# Predajnik.net
KiCad netlist of a schematic drawn in Altium Designer
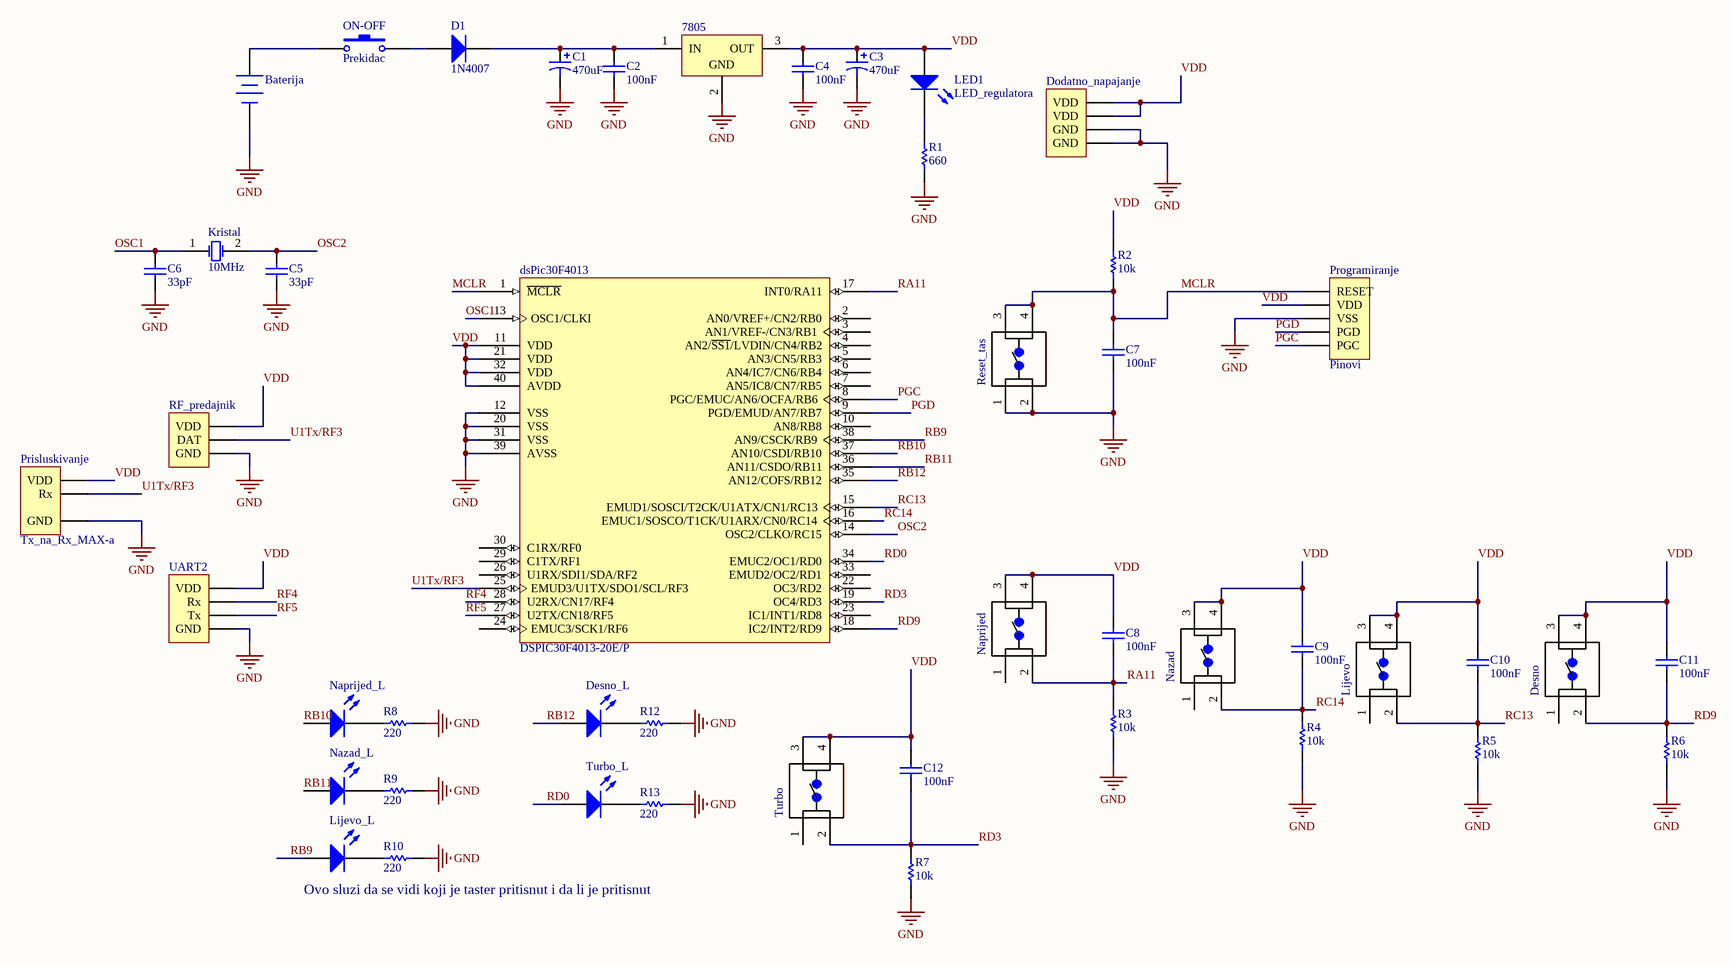
[diagram p0: Predajnik.SchDoc]

(export (version "E")
  (design (tool "Eeschema 10.0.6"))
  (components
    (comp (ref "7805")
      (value "LM7805CT")
      (footprint "T03B")
      (description "3-Terminal Negative Regulator, 3-pin TO-220")
      (fields
        (field (name "PARTNUMBER") "LM7905CT")
        (field (name "MANUFACTURER") "National Semiconductor")
        (field (name "PUBLISHER") "Altium Limited")
      )
      (libsource (lib "NSC LDO") (part "LM7905CT"))
    )
    (comp (ref "Baterija")
      (value "9V")
      (footprint "BAT-2")
      (description "Multicell Battery")
      (fields (field (name "PUBLISHER") "Altium Limited"))
      (libsource (lib "Miscellaneous Devices") (part "Battery"))
    )
    (comp (ref "C1")
      (value "470uF")
      (footprint "El. Kondenzator 470uf")
      (description "Polarized Capacitor (Radial)")
      (fields (field (name "PUBLISHER") "Altium Limited"))
      (libsource (lib "Miscellaneous Devices") (part "Cap Pol1"))
    )
    (comp (ref "C2")
      (value "100nF")
      (footprint "C blok 100n")
      (description "Capacitor")
      (fields (field (name "PUBLISHER") "Altium Limited"))
      (libsource (lib "Miscellaneous Devices") (part "Cap"))
    )
    (comp (ref "C3")
      (value "470uF")
      (footprint "El. Kondenzator 470uf")
      (description "Polarized Capacitor (Radial)")
      (fields (field (name "PUBLISHER") "Altium Limited"))
      (libsource (lib "Miscellaneous Devices") (part "Cap Pol1"))
    )
    (comp (ref "C4")
      (value "100nF")
      (footprint "C blok 100n")
      (description "Capacitor")
      (fields (field (name "PUBLISHER") "Altium Limited"))
      (libsource (lib "Miscellaneous Devices") (part "Cap"))
    )
    (comp (ref "C5")
      (value "33pF")
      (footprint "C keramicki 30pF")
      (description "Capacitor")
      (fields (field (name "PUBLISHER") "Altium Limited"))
      (libsource (lib "Miscellaneous Devices") (part "Cap"))
    )
    (comp (ref "C6")
      (value "33pF")
      (footprint "C keramicki 30pF")
      (description "Capacitor")
      (fields (field (name "PUBLISHER") "Altium Limited"))
      (libsource (lib "Miscellaneous Devices") (part "Cap"))
    )
    (comp (ref "C7")
      (value "100nF")
      (footprint "C blok 100n")
      (description "Capacitor")
      (fields (field (name "PUBLISHER") "Altium Limited"))
      (libsource (lib "Miscellaneous Devices") (part "Cap"))
    )
    (comp (ref "C8")
      (value "100nF")
      (footprint "C blok 100n")
      (description "Capacitor")
      (fields (field (name "PUBLISHER") "Altium Limited"))
      (libsource (lib "Miscellaneous Devices") (part "Cap"))
    )
    (comp (ref "C9")
      (value "100nF")
      (footprint "C blok 100n")
      (description "Capacitor")
      (fields (field (name "PUBLISHER") "Altium Limited"))
      (libsource (lib "Miscellaneous Devices") (part "Cap"))
    )
    (comp (ref "C10")
      (value "100nF")
      (footprint "C blok 100n")
      (description "Capacitor")
      (fields (field (name "PUBLISHER") "Altium Limited"))
      (libsource (lib "Miscellaneous Devices") (part "Cap"))
    )
    (comp (ref "C11")
      (value "100nF")
      (footprint "C blok 100n")
      (description "Capacitor")
      (fields (field (name "PUBLISHER") "Altium Limited"))
      (libsource (lib "Miscellaneous Devices") (part "Cap"))
    )
    (comp (ref "C12")
      (value "100nF")
      (footprint "C blok 100n")
      (description "Capacitor")
      (fields (field (name "PUBLISHER") "Altium Limited"))
      (libsource (lib "Miscellaneous Devices") (part "Cap"))
    )
    (comp (ref "D1")
      (value "1N4007")
      (footprint "DO-41")
      (description "1 Amp General Purpose Rectifier")
      (fields (field (name "PUBLISHER") "Altium Limited"))
      (libsource (lib "Miscellaneous Devices") (part "Diode 1N4007"))
    )
    (comp (ref "Desno")
      (value "3-1825910-1")
      (footprint "*TE_3-1825910-1")
      (description "Switch Push Button OFF _ON_ SPST Round Button 0.05A 24VDC Momentary Contact PC Pins Thru-Hole")
      (fields (field (name "MF") "TE Connectivity"))
      (libsource (lib "3-1825910-1") (part "3-1825910-1"))
    )
    (comp (ref "Desno_L")
      (value "LED0")
      (footprint "LED_5mm")
      (description "Typical INFRARED GaAs LED")
      (fields (field (name "PUBLISHER") "Altium Limited"))
      (libsource (lib "Miscellaneous Devices") (part "LED0"))
    )
    (comp (ref "Dodatno_napajanje")
      (value "~")
      (footprint "HDR1X4")
      (description "Header, 4-Pin")
      (fields (field (name "PUBLISHER") "Altium Limited"))
      (libsource (lib "") (part "Header 4_2"))
    )
    (comp (ref "dsPic30F4013")
      (value "DSPIC30F4013-20E/P")
      (footprint "PDIP600-P40")
      (fields (field (name "PUBLISHER") "Altium Limited"))
      (libsource (lib "Microchip DSC 16-Bit dsPIC30F") (part "DSPIC30F4013-20E/P"))
    )
    (comp (ref "Kristal")
      (value "10MHz")
      (footprint "R38")
      (description "Crystal Oscillator")
      (fields (field (name "PUBLISHER") "Altium Limited"))
      (libsource (lib "Miscellaneous Devices") (part "XTAL"))
    )
    (comp (ref "LED1")
      (value "LED_regulatora")
      (footprint "LED_5mm")
      (description "Typical RED GaAs LED")
      (fields (field (name "PUBLISHER") "Altium Limited"))
      (libsource (lib "Miscellaneous Devices") (part "LED1"))
    )
    (comp (ref "Lijevo")
      (value "3-1825910-1")
      (footprint "*TE_3-1825910-1")
      (description "Switch Push Button OFF _ON_ SPST Round Button 0.05A 24VDC Momentary Contact PC Pins Thru-Hole")
      (fields (field (name "MF") "TE Connectivity"))
      (libsource (lib "3-1825910-1") (part "3-1825910-1"))
    )
    (comp (ref "Lijevo_L")
      (value "LED0")
      (footprint "LED_5mm")
      (description "Typical INFRARED GaAs LED")
      (fields (field (name "PUBLISHER") "Altium Limited"))
      (libsource (lib "Miscellaneous Devices") (part "LED0"))
    )
    (comp (ref "Naprijed")
      (value "3-1825910-1")
      (footprint "*TE_3-1825910-1")
      (description "Switch Push Button OFF _ON_ SPST Round Button 0.05A 24VDC Momentary Contact PC Pins Thru-Hole")
      (fields (field (name "MF") "TE Connectivity"))
      (libsource (lib "3-1825910-1") (part "3-1825910-1"))
    )
    (comp (ref "Naprijed_L")
      (value "LED0")
      (footprint "LED_5mm")
      (description "Typical INFRARED GaAs LED")
      (fields (field (name "PUBLISHER") "Altium Limited"))
      (libsource (lib "Miscellaneous Devices") (part "LED0"))
    )
    (comp (ref "Nazad")
      (value "3-1825910-1")
      (footprint "*TE_3-1825910-1")
      (description "Switch Push Button OFF _ON_ SPST Round Button 0.05A 24VDC Momentary Contact PC Pins Thru-Hole")
      (fields (field (name "MF") "TE Connectivity"))
      (libsource (lib "3-1825910-1") (part "3-1825910-1"))
    )
    (comp (ref "Nazad_L")
      (value "LED0")
      (footprint "LED_5mm")
      (description "Typical INFRARED GaAs LED")
      (fields (field (name "PUBLISHER") "Altium Limited"))
      (libsource (lib "Miscellaneous Devices") (part "LED0"))
    )
    (comp (ref "ON-OFF")
      (value "Prekidac")
      (footprint "SPST-2")
      (description "Switch")
      (fields (field (name "PUBLISHER") "Altium Limited"))
      (libsource (lib "Miscellaneous Devices") (part "SW-PB"))
    )
    (comp (ref "Prisluskivanje")
      (value "Tx_na_Rx_MAX-a")
      (footprint "HDR1X3")
      (description "Header, 4-Pin")
      (fields (field (name "PUBLISHER") "Altium Limited"))
      (libsource (lib "Miscellaneous Connectors") (part "Header 4"))
    )
    (comp (ref "Programiranje")
      (value "Pinovi")
      (footprint "HDR1X5")
      (description "Header, 5-Pin")
      (fields (field (name "PUBLISHER") "Altium Limited"))
      (libsource (lib "Miscellaneous Connectors") (part "Header 5"))
    )
    (comp (ref "R1")
      (value "660")
      (footprint "AXIAL-0.3")
      (description "Resistor")
      (fields (field (name "PUBLISHER") "Altium Limited"))
      (libsource (lib "Miscellaneous Devices") (part "Res1"))
    )
    (comp (ref "R2")
      (value "10k")
      (footprint "AXIAL-0.3")
      (description "Resistor")
      (fields (field (name "PUBLISHER") "Altium Limited"))
      (libsource (lib "Miscellaneous Devices") (part "Res1"))
    )
    (comp (ref "R3")
      (value "10k")
      (footprint "AXIAL-0.3")
      (description "Resistor")
      (fields (field (name "PUBLISHER") "Altium Limited"))
      (libsource (lib "Miscellaneous Devices") (part "Res1"))
    )
    (comp (ref "R4")
      (value "10k")
      (footprint "AXIAL-0.3")
      (description "Resistor")
      (fields (field (name "PUBLISHER") "Altium Limited"))
      (libsource (lib "Miscellaneous Devices") (part "Res1"))
    )
    (comp (ref "R5")
      (value "10k")
      (footprint "AXIAL-0.3")
      (description "Resistor")
      (fields (field (name "PUBLISHER") "Altium Limited"))
      (libsource (lib "Miscellaneous Devices") (part "Res1"))
    )
    (comp (ref "R6")
      (value "10k")
      (footprint "AXIAL-0.3")
      (description "Resistor")
      (fields (field (name "PUBLISHER") "Altium Limited"))
      (libsource (lib "Miscellaneous Devices") (part "Res1"))
    )
    (comp (ref "R7")
      (value "10k")
      (footprint "AXIAL-0.3")
      (description "Resistor")
      (fields (field (name "PUBLISHER") "Altium Limited"))
      (libsource (lib "Miscellaneous Devices") (part "Res1"))
    )
    (comp (ref "R8")
      (value "220")
      (footprint "AXIAL-0.3")
      (description "Resistor")
      (fields (field (name "PUBLISHER") "Altium Limited"))
      (libsource (lib "Miscellaneous Devices") (part "Res1"))
    )
    (comp (ref "R9")
      (value "220")
      (footprint "AXIAL-0.3")
      (description "Resistor")
      (fields (field (name "PUBLISHER") "Altium Limited"))
      (libsource (lib "Miscellaneous Devices") (part "Res1"))
    )
    (comp (ref "R10")
      (value "220")
      (footprint "AXIAL-0.3")
      (description "Resistor")
      (fields (field (name "PUBLISHER") "Altium Limited"))
      (libsource (lib "Miscellaneous Devices") (part "Res1"))
    )
    (comp (ref "R12")
      (value "220")
      (footprint "AXIAL-0.3")
      (description "Resistor")
      (fields (field (name "PUBLISHER") "Altium Limited"))
      (libsource (lib "Miscellaneous Devices") (part "Res1"))
    )
    (comp (ref "R13")
      (value "220")
      (footprint "AXIAL-0.3")
      (description "Resistor")
      (fields (field (name "PUBLISHER") "Altium Limited"))
      (libsource (lib "Miscellaneous Devices") (part "Res1"))
    )
    (comp (ref "Reset_tas")
      (value "3-1825910-1")
      (footprint "*TE_3-1825910-1")
      (description "Switch Push Button OFF _ON_ SPST Round Button 0.05A 24VDC Momentary Contact PC Pins Thru-Hole")
      (fields (field (name "MF") "TE Connectivity"))
      (libsource (lib "3-1825910-1") (part "3-1825910-1"))
    )
    (comp (ref "RF_predajnik")
      (value "Header 3")
      (footprint "HDR1X3")
      (description "Header, 3-Pin")
      (fields (field (name "PUBLISHER") "Altium Limited"))
      (libsource (lib "Miscellaneous Connectors") (part "Header 3"))
    )
    (comp (ref "Turbo")
      (value "3-1825910-1")
      (footprint "*TE_3-1825910-1")
      (description "Switch Push Button OFF _ON_ SPST Round Button 0.05A 24VDC Momentary Contact PC Pins Thru-Hole")
      (fields (field (name "MF") "TE Connectivity"))
      (libsource (lib "3-1825910-1") (part "3-1825910-1"))
    )
    (comp (ref "Turbo_L")
      (value "LED0")
      (footprint "LED_5mm")
      (description "Typical INFRARED GaAs LED")
      (fields (field (name "PUBLISHER") "Altium Limited"))
      (libsource (lib "Miscellaneous Devices") (part "LED0"))
    )
    (comp (ref "UART2")
      (value "~")
      (footprint "HDR1X4")
      (description "Header, 4-Pin")
      (fields (field (name "PUBLISHER") "Altium Limited"))
      (libsource (lib "") (part "Header 4_1"))
    )
  )
  (nets
    (net (code "1") (name "/MCLR") (class "Default")
      (node (ref "C7") (pin "2") (pinfunction "2_2") (pintype "passive"))
      (node (ref "Programiranje") (pin "1") (pinfunction "RESET_1") (pintype "passive"))
      (node (ref "R2") (pin "1") (pinfunction "1_1") (pintype "passive"))
      (node (ref "Reset_tas") (pin "3") (pinfunction "3_3") (pintype "passive"))
      (node (ref "Reset_tas") (pin "4") (pinfunction "4_4") (pintype "passive"))
      (node (ref "dsPic30F4013") (pin "1") (pinfunction "~{MCLR}_1") (pintype "input"))
    )
    (net (code "2") (name "/OSC1") (class "Default")
      (node (ref "C6") (pin "2") (pinfunction "2_2") (pintype "passive"))
      (node (ref "Kristal") (pin "1") (pinfunction "OSC1_1") (pintype "passive"))
      (node (ref "dsPic30F4013") (pin "13") (pinfunction "OSC1/CLKI_13") (pintype "input"))
    )
    (net (code "3") (name "/OSC2") (class "Default")
      (node (ref "C5") (pin "2") (pinfunction "2_2") (pintype "passive"))
      (node (ref "Kristal") (pin "2") (pinfunction "OSC2_2") (pintype "passive"))
      (node (ref "dsPic30F4013") (pin "14") (pinfunction "OSC2/CLKO/RC15_14") (pintype "bidirectional"))
    )
    (net (code "4") (name "/PGC") (class "Default")
      (node (ref "Programiranje") (pin "5") (pinfunction "PGC_5") (pintype "passive"))
      (node (ref "dsPic30F4013") (pin "8") (pinfunction "PGC/EMUC/AN6/OCFA/RB6_8") (pintype "bidirectional"))
    )
    (net (code "5") (name "/PGD") (class "Default")
      (node (ref "Programiranje") (pin "4") (pinfunction "PGD_4") (pintype "passive"))
      (node (ref "dsPic30F4013") (pin "9") (pinfunction "PGD/EMUD/AN7/RB7_9") (pintype "bidirectional"))
    )
    (net (code "6") (name "/RA11") (class "Default")
      (node (ref "C8") (pin "1") (pinfunction "1_1") (pintype "passive"))
      (node (ref "Naprijed") (pin "2") (pinfunction "2_2") (pintype "passive"))
      (node (ref "R3") (pin "2") (pinfunction "2_2") (pintype "passive"))
      (node (ref "dsPic30F4013") (pin "17") (pinfunction "INT0/RA11_17") (pintype "bidirectional"))
    )
    (net (code "7") (name "/RB9") (class "Default")
      (node (ref "Lijevo_L") (pin "1") (pinfunction "A_1") (pintype "passive"))
      (node (ref "dsPic30F4013") (pin "38") (pinfunction "AN9/CSCK/RB9_38") (pintype "bidirectional"))
    )
    (net (code "8") (name "/RB10") (class "Default")
      (node (ref "Naprijed_L") (pin "1") (pinfunction "A_1") (pintype "passive"))
      (node (ref "dsPic30F4013") (pin "37") (pinfunction "AN10/CSDI/RB10_37") (pintype "bidirectional"))
    )
    (net (code "9") (name "/RB11") (class "Default")
      (node (ref "Nazad_L") (pin "1") (pinfunction "A_1") (pintype "passive"))
      (node (ref "dsPic30F4013") (pin "36") (pinfunction "AN11/CSDO/RB11_36") (pintype "bidirectional"))
    )
    (net (code "10") (name "/RB12") (class "Default")
      (node (ref "Desno_L") (pin "1") (pinfunction "A_1") (pintype "passive"))
      (node (ref "dsPic30F4013") (pin "35") (pinfunction "AN12/COFS/RB12_35") (pintype "bidirectional"))
    )
    (net (code "11") (name "/RC13") (class "Default")
      (node (ref "C10") (pin "1") (pinfunction "1_1") (pintype "passive"))
      (node (ref "Lijevo") (pin "2") (pinfunction "2_2") (pintype "passive"))
      (node (ref "R5") (pin "2") (pinfunction "2_2") (pintype "passive"))
      (node (ref "dsPic30F4013") (pin "15") (pinfunction "EMUD1/SOSCI/T2CK/U1ATX/CN1/RC13_15") (pintype "bidirectional"))
    )
    (net (code "12") (name "/RC14") (class "Default")
      (node (ref "C9") (pin "1") (pinfunction "1_1") (pintype "passive"))
      (node (ref "Nazad") (pin "2") (pinfunction "2_2") (pintype "passive"))
      (node (ref "R4") (pin "2") (pinfunction "2_2") (pintype "passive"))
      (node (ref "dsPic30F4013") (pin "16") (pinfunction "EMUC1/SOSCO/T1CK/U1ARX/CN0/RC14_16") (pintype "bidirectional"))
    )
    (net (code "13") (name "/RD0") (class "Default")
      (node (ref "Turbo_L") (pin "1") (pinfunction "A_1") (pintype "passive"))
      (node (ref "dsPic30F4013") (pin "34") (pinfunction "EMUC2/OC1/RD0_34") (pintype "bidirectional"))
    )
    (net (code "14") (name "/RD3") (class "Default")
      (node (ref "C12") (pin "1") (pinfunction "1_1") (pintype "passive"))
      (node (ref "R7") (pin "2") (pinfunction "2_2") (pintype "passive"))
      (node (ref "Turbo") (pin "2") (pinfunction "2_2") (pintype "passive"))
      (node (ref "dsPic30F4013") (pin "19") (pinfunction "OC4/RD3_19") (pintype "bidirectional"))
    )
    (net (code "15") (name "/RD9") (class "Default")
      (node (ref "C11") (pin "1") (pinfunction "1_1") (pintype "passive"))
      (node (ref "Desno") (pin "2") (pinfunction "2_2") (pintype "passive"))
      (node (ref "R6") (pin "2") (pinfunction "2_2") (pintype "passive"))
      (node (ref "dsPic30F4013") (pin "18") (pinfunction "IC2/INT2/RD9_18") (pintype "bidirectional"))
    )
    (net (code "16") (name "/RF4") (class "Default")
      (node (ref "UART2") (pin "2") (pinfunction "Rx_2") (pintype "passive"))
      (node (ref "dsPic30F4013") (pin "28") (pinfunction "U2RX/CN17/RF4_28") (pintype "bidirectional"))
    )
    (net (code "17") (name "/RF5") (class "Default")
      (node (ref "UART2") (pin "3") (pinfunction "Tx_3") (pintype "passive"))
      (node (ref "dsPic30F4013") (pin "27") (pinfunction "U2TX/CN18/RF5_27") (pintype "bidirectional"))
    )
    (net (code "18") (name "/U1Tx{slash}RF3") (class "Default")
      (node (ref "Prisluskivanje") (pin "2") (pinfunction "Rx_2") (pintype "passive"))
      (node (ref "RF_predajnik") (pin "2") (pinfunction "DAT_2") (pintype "passive"))
      (node (ref "dsPic30F4013") (pin "25") (pinfunction "EMUD3/U1TX/SDO1/SCL/RF3_25") (pintype "bidirectional"))
    )
    (net (code "19") (name "/VDD") (class "Default")
      (node (ref "7805") (pin "3") (pinfunction "OUT_3") (pintype "power_in"))
      (node (ref "C10") (pin "2") (pinfunction "2_2") (pintype "passive"))
      (node (ref "C11") (pin "2") (pinfunction "2_2") (pintype "passive"))
      (node (ref "C12") (pin "2") (pinfunction "2_2") (pintype "passive"))
      (node (ref "C3") (pin "1") (pinfunction "1_1") (pintype "passive"))
      (node (ref "C4") (pin "2") (pinfunction "2_2") (pintype "passive"))
      (node (ref "C8") (pin "2") (pinfunction "2_2") (pintype "passive"))
      (node (ref "C9") (pin "2") (pinfunction "2_2") (pintype "passive"))
      (node (ref "Desno") (pin "3") (pinfunction "3_3") (pintype "passive"))
      (node (ref "Desno") (pin "4") (pinfunction "4_4") (pintype "passive"))
      (node (ref "Dodatno_napajanje") (pin "1") (pinfunction "VDD_1") (pintype "passive"))
      (node (ref "Dodatno_napajanje") (pin "2") (pinfunction "VDD_2") (pintype "passive"))
      (node (ref "LED1") (pin "1") (pinfunction "A_1") (pintype "passive"))
      (node (ref "Lijevo") (pin "3") (pinfunction "3_3") (pintype "passive"))
      (node (ref "Lijevo") (pin "4") (pinfunction "4_4") (pintype "passive"))
      (node (ref "Naprijed") (pin "3") (pinfunction "3_3") (pintype "passive"))
      (node (ref "Naprijed") (pin "4") (pinfunction "4_4") (pintype "passive"))
      (node (ref "Nazad") (pin "3") (pinfunction "3_3") (pintype "passive"))
      (node (ref "Nazad") (pin "4") (pinfunction "4_4") (pintype "passive"))
      (node (ref "Prisluskivanje") (pin "1") (pinfunction "VDD_1") (pintype "passive"))
      (node (ref "Programiranje") (pin "2") (pinfunction "VDD_2") (pintype "passive"))
      (node (ref "R2") (pin "2") (pinfunction "2_2") (pintype "passive"))
      (node (ref "RF_predajnik") (pin "1") (pinfunction "VDD_1") (pintype "passive"))
      (node (ref "Turbo") (pin "3") (pinfunction "3_3") (pintype "passive"))
      (node (ref "Turbo") (pin "4") (pinfunction "4_4") (pintype "passive"))
      (node (ref "UART2") (pin "1") (pinfunction "VDD_1") (pintype "passive"))
      (node (ref "dsPic30F4013") (pin "11") (pinfunction "VDD_11") (pintype "power_in"))
      (node (ref "dsPic30F4013") (pin "21") (pinfunction "VDD_21") (pintype "power_in"))
      (node (ref "dsPic30F4013") (pin "32") (pinfunction "VDD_32") (pintype "power_in"))
      (node (ref "dsPic30F4013") (pin "40") (pinfunction "AVDD_40") (pintype "power_in"))
    )
    (net (code "20") (name "GND") (class "Default")
      (node (ref "7805") (pin "2") (pinfunction "GND_2") (pintype "power_in"))
      (node (ref "Baterija") (pin "2") (pinfunction "-_2") (pintype "passive"))
      (node (ref "C1") (pin "2") (pinfunction "2_2") (pintype "passive"))
      (node (ref "C2") (pin "1") (pinfunction "1_1") (pintype "passive"))
      (node (ref "C3") (pin "2") (pinfunction "2_2") (pintype "passive"))
      (node (ref "C4") (pin "1") (pinfunction "1_1") (pintype "passive"))
      (node (ref "C5") (pin "1") (pinfunction "1_1") (pintype "passive"))
      (node (ref "C6") (pin "1") (pinfunction "1_1") (pintype "passive"))
      (node (ref "C7") (pin "1") (pinfunction "1_1") (pintype "passive"))
      (node (ref "Dodatno_napajanje") (pin "3") (pinfunction "GND_3") (pintype "passive"))
      (node (ref "Dodatno_napajanje") (pin "4") (pinfunction "GND_4") (pintype "passive"))
      (node (ref "Prisluskivanje") (pin "3") (pinfunction "GND_3") (pintype "passive"))
      (node (ref "Programiranje") (pin "3") (pinfunction "VSS_3") (pintype "passive"))
      (node (ref "R1") (pin "1") (pinfunction "1_1") (pintype "passive"))
      (node (ref "R10") (pin "2") (pinfunction "2_2") (pintype "passive"))
      (node (ref "R12") (pin "2") (pinfunction "2_2") (pintype "passive"))
      (node (ref "R13") (pin "2") (pinfunction "2_2") (pintype "passive"))
      (node (ref "R3") (pin "1") (pinfunction "1_1") (pintype "passive"))
      (node (ref "R4") (pin "1") (pinfunction "1_1") (pintype "passive"))
      (node (ref "R5") (pin "1") (pinfunction "1_1") (pintype "passive"))
      (node (ref "R6") (pin "1") (pinfunction "1_1") (pintype "passive"))
      (node (ref "R7") (pin "1") (pinfunction "1_1") (pintype "passive"))
      (node (ref "R8") (pin "2") (pinfunction "2_2") (pintype "passive"))
      (node (ref "R9") (pin "2") (pinfunction "2_2") (pintype "passive"))
      (node (ref "RF_predajnik") (pin "3") (pinfunction "GND_3") (pintype "passive"))
      (node (ref "Reset_tas") (pin "1") (pinfunction "1_1") (pintype "passive"))
      (node (ref "Reset_tas") (pin "2") (pinfunction "2_2") (pintype "passive"))
      (node (ref "UART2") (pin "4") (pinfunction "GND_4") (pintype "passive"))
      (node (ref "dsPic30F4013") (pin "12") (pinfunction "VSS_12") (pintype "power_in"))
      (node (ref "dsPic30F4013") (pin "20") (pinfunction "VSS_20") (pintype "power_in"))
      (node (ref "dsPic30F4013") (pin "31") (pinfunction "VSS_31") (pintype "power_in"))
      (node (ref "dsPic30F4013") (pin "39") (pinfunction "AVSS_39") (pintype "power_in"))
    )
    (net (code "21") (name "Net-(7805-IN)") (class "Default")
      (node (ref "7805") (pin "1") (pinfunction "IN_1") (pintype "power_in"))
      (node (ref "C1") (pin "1") (pinfunction "1_1") (pintype "passive"))
      (node (ref "C2") (pin "2") (pinfunction "2_2") (pintype "passive"))
      (node (ref "D1") (pin "2") (pinfunction "K_2") (pintype "passive"))
    )
    (net (code "22") (name "Net-(Baterija-+)") (class "Default")
      (node (ref "Baterija") (pin "1") (pinfunction "+_1") (pintype "passive"))
      (node (ref "ON-OFF") (pin "1") (pinfunction "1_1") (pintype "passive"))
    )
    (net (code "23") (name "Net-(D1-A)") (class "Default")
      (node (ref "D1") (pin "1") (pinfunction "A_1") (pintype "passive"))
      (node (ref "ON-OFF") (pin "2") (pinfunction "2_2") (pintype "passive"))
    )
    (net (code "24") (name "Net-(Desno_L-K)") (class "Default")
      (node (ref "Desno_L") (pin "2") (pinfunction "K_2") (pintype "passive"))
      (node (ref "R12") (pin "1") (pinfunction "1_1") (pintype "passive"))
    )
    (net (code "25") (name "Net-(LED1-K)") (class "Default")
      (node (ref "LED1") (pin "2") (pinfunction "K_2") (pintype "passive"))
      (node (ref "R1") (pin "2") (pinfunction "2_2") (pintype "passive"))
    )
    (net (code "26") (name "Net-(Lijevo_L-K)") (class "Default")
      (node (ref "Lijevo_L") (pin "2") (pinfunction "K_2") (pintype "passive"))
      (node (ref "R10") (pin "1") (pinfunction "1_1") (pintype "passive"))
    )
    (net (code "27") (name "Net-(Naprijed_L-K)") (class "Default")
      (node (ref "Naprijed_L") (pin "2") (pinfunction "K_2") (pintype "passive"))
      (node (ref "R8") (pin "1") (pinfunction "1_1") (pintype "passive"))
    )
    (net (code "28") (name "Net-(Nazad_L-K)") (class "Default")
      (node (ref "Nazad_L") (pin "2") (pinfunction "K_2") (pintype "passive"))
      (node (ref "R9") (pin "1") (pinfunction "1_1") (pintype "passive"))
    )
    (net (code "29") (name "Net-(Turbo_L-K)") (class "Default")
      (node (ref "R13") (pin "1") (pinfunction "1_1") (pintype "passive"))
      (node (ref "Turbo_L") (pin "2") (pinfunction "K_2") (pintype "passive"))
    )
    (net (code "30") (name "unconnected-(Desno-Pad1)") (class "Default")
      (node (ref "Desno") (pin "1") (pinfunction "1_1") (pintype "passive"))
    )
    (net (code "31") (name "unconnected-(Lijevo-Pad1)") (class "Default")
      (node (ref "Lijevo") (pin "1") (pinfunction "1_1") (pintype "passive"))
    )
    (net (code "32") (name "unconnected-(Naprijed-Pad1)") (class "Default")
      (node (ref "Naprijed") (pin "1") (pinfunction "1_1") (pintype "passive"))
    )
    (net (code "33") (name "unconnected-(Nazad-Pad1)") (class "Default")
      (node (ref "Nazad") (pin "1") (pinfunction "1_1") (pintype "passive"))
    )
    (net (code "34") (name "unconnected-(Turbo-Pad1)") (class "Default")
      (node (ref "Turbo") (pin "1") (pinfunction "1_1") (pintype "passive"))
    )
    (net (code "35") (name "unconnected-(dsPic30F4013-AN0{slash}VREF+{slash}CN2{slash}RB0-Pad2)") (class "Default")
      (node (ref "dsPic30F4013") (pin "2") (pinfunction "AN0/VREF+/CN2/RB0_2") (pintype "bidirectional"))
    )
    (net (code "36") (name "unconnected-(dsPic30F4013-AN1{slash}VREF-{slash}CN3{slash}RB1-Pad3)") (class "Default")
      (node (ref "dsPic30F4013") (pin "3") (pinfunction "AN1/VREF-/CN3/RB1_3") (pintype "bidirectional"))
    )
    (net (code "37") (name "unconnected-(dsPic30F4013-AN2{slash}~{SS1}{slash}LVDIN{slash}CN4{slash}RB2-Pad4)") (class "Default")
      (node (ref "dsPic30F4013") (pin "4") (pinfunction "AN2/~{SS1}/LVDIN/CN4/RB2_4") (pintype "bidirectional"))
    )
    (net (code "38") (name "unconnected-(dsPic30F4013-AN3{slash}CN5{slash}RB3-Pad5)") (class "Default")
      (node (ref "dsPic30F4013") (pin "5") (pinfunction "AN3/CN5/RB3_5") (pintype "bidirectional"))
    )
    (net (code "39") (name "unconnected-(dsPic30F4013-AN4{slash}IC7{slash}CN6{slash}RB4-Pad6)") (class "Default")
      (node (ref "dsPic30F4013") (pin "6") (pinfunction "AN4/IC7/CN6/RB4_6") (pintype "bidirectional"))
    )
    (net (code "40") (name "unconnected-(dsPic30F4013-AN5{slash}IC8{slash}CN7{slash}RB5-Pad7)") (class "Default")
      (node (ref "dsPic30F4013") (pin "7") (pinfunction "AN5/IC8/CN7/RB5_7") (pintype "bidirectional"))
    )
    (net (code "41") (name "unconnected-(dsPic30F4013-AN8{slash}RB8-Pad10)") (class "Default")
      (node (ref "dsPic30F4013") (pin "10") (pinfunction "AN8/RB8_10") (pintype "bidirectional"))
    )
    (net (code "42") (name "unconnected-(dsPic30F4013-C1RX{slash}RF0-Pad30)") (class "Default")
      (node (ref "dsPic30F4013") (pin "30") (pinfunction "C1RX/RF0_30") (pintype "bidirectional"))
    )
    (net (code "43") (name "unconnected-(dsPic30F4013-C1TX{slash}RF1-Pad29)") (class "Default")
      (node (ref "dsPic30F4013") (pin "29") (pinfunction "C1TX/RF1_29") (pintype "bidirectional"))
    )
    (net (code "44") (name "unconnected-(dsPic30F4013-EMUC3{slash}SCK1{slash}RF6-Pad24)") (class "Default")
      (node (ref "dsPic30F4013") (pin "24") (pinfunction "EMUC3/SCK1/RF6_24") (pintype "bidirectional"))
    )
    (net (code "45") (name "unconnected-(dsPic30F4013-EMUD2{slash}OC2{slash}RD1-Pad33)") (class "Default")
      (node (ref "dsPic30F4013") (pin "33") (pinfunction "EMUD2/OC2/RD1_33") (pintype "bidirectional"))
    )
    (net (code "46") (name "unconnected-(dsPic30F4013-IC1{slash}INT1{slash}RD8-Pad23)") (class "Default")
      (node (ref "dsPic30F4013") (pin "23") (pinfunction "IC1/INT1/RD8_23") (pintype "bidirectional"))
    )
    (net (code "47") (name "unconnected-(dsPic30F4013-OC3{slash}RD2-Pad22)") (class "Default")
      (node (ref "dsPic30F4013") (pin "22") (pinfunction "OC3/RD2_22") (pintype "bidirectional"))
    )
    (net (code "48") (name "unconnected-(dsPic30F4013-U1RX{slash}SDI1{slash}SDA{slash}RF2-Pad26)") (class "Default")
      (node (ref "dsPic30F4013") (pin "26") (pinfunction "U1RX/SDI1/SDA/RF2_26") (pintype "bidirectional"))
    )
  )
)
